# PowerSupply.net
KiCad netlist of a schematic drawn in Altium Designer
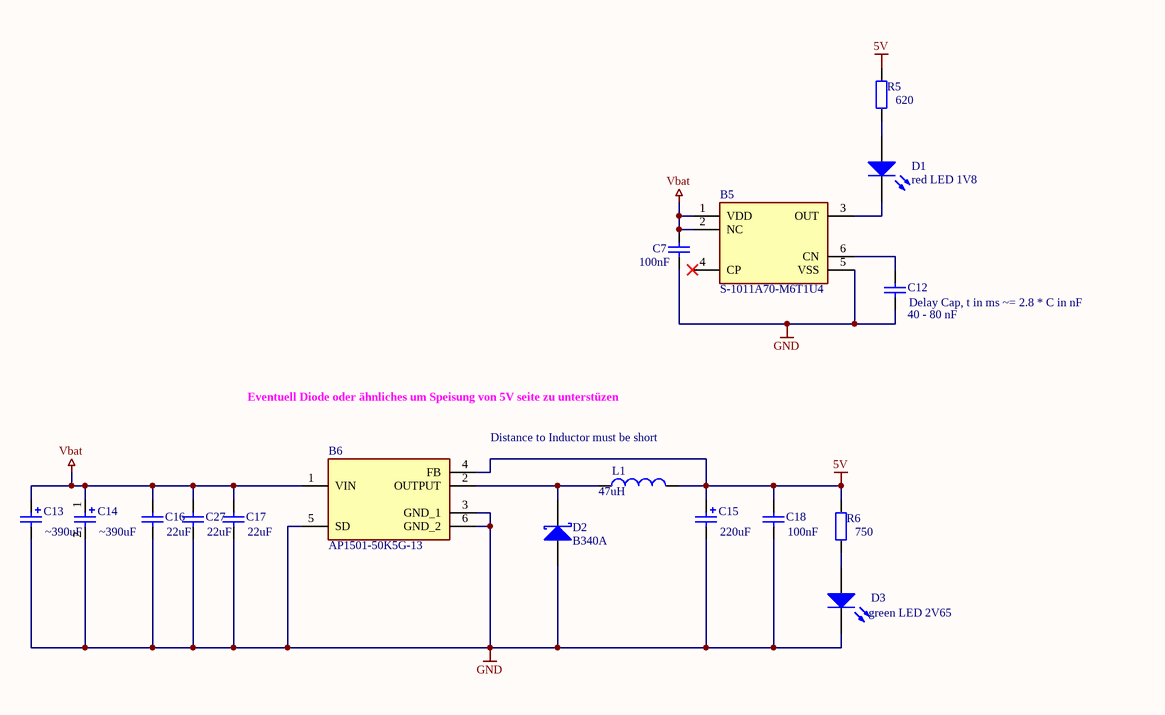
[diagram p0: PowerSupply.SchDoc]

(export (version "E")
  (design (tool "Eeschema 10.0.6"))
  (components
    (comp (ref "B5")
      (value "S-1011A70-M6T1U4")
      (footprint "SOT95P275X135-6N")
      (description "Supervisory Circuits VOLTAGE DETECTOR")
      (fields (field (name "MOUSER PART NUMBER") "628-S-1011A70-M6T1U4"))
      (libsource (lib "SchematicLib") (part "S-1011A70-M6T1U4"))
    )
    (comp (ref "B6")
      (value "AP1501-50K5G-13")
      (footprint "AP150150K5G13")
      (description "IC REG BUCK 5V 3A TO263-5")
      (fields (field (name "MOUSER PART NUMBER") "621-AP1501-50K5G-13"))
      (libsource (lib "SchematicLib") (part "AP1501-50K5G-13"))
    )
    (comp (ref "C7")
      (value "100nF")
      (footprint "0805_Lorin")
      (description "Capacitor")
      (fields (field (name "Comment") "Cap") (field (name "PUBLISHER") "Altium Limited"))
      (libsource (lib "Miscellaneous Devices") (part "Cap"))
    )
    (comp (ref "C12")
      (value "40 - 80 nF")
      (footprint "0805_Lorin")
      (description "Capacitor")
      (fields (field (name "Comment") "Cap") (field (name "PUBLISHER") "Altium Limited"))
      (libsource (lib "Miscellaneous Devices") (part "Cap"))
    )
    (comp (ref "C13")
      (value "~390uF")
      (footprint "CAP390uF")
      (description "Polarized Capacitor (Axial)")
      (fields (field (name "Comment") "Cap Pol2") (field (name "PUBLISHER") "Altium Limited"))
      (libsource (lib "Miscellaneous Devices") (part "Cap Pol2"))
    )
    (comp (ref "C14")
      (value "~390uF")
      (footprint "CAP390uF")
      (description "Polarized Capacitor (Axial)")
      (fields (field (name "Comment") "Cap Pol2") (field (name "PUBLISHER") "Altium Limited"))
      (libsource (lib "") (part "Cap Pol2_1"))
    )
    (comp (ref "C15")
      (value "220uF")
      (footprint "CAP220uF")
      (description "Polarized Capacitor (Axial)")
      (fields (field (name "Comment") "Cap Pol2") (field (name "PUBLISHER") "Altium Limited"))
      (libsource (lib "Miscellaneous Devices") (part "Cap Pol2"))
    )
    (comp (ref "C16")
      (value "22uF")
      (footprint "0805_Lorin")
      (description "Capacitor")
      (fields (field (name "Comment") "Cap") (field (name "PUBLISHER") "Altium Limited"))
      (libsource (lib "Miscellaneous Devices") (part "Cap"))
    )
    (comp (ref "C17")
      (value "22uF")
      (footprint "0805_Lorin")
      (description "Capacitor")
      (fields (field (name "Comment") "Cap") (field (name "PUBLISHER") "Altium Limited"))
      (libsource (lib "Miscellaneous Devices") (part "Cap"))
    )
    (comp (ref "C18")
      (value "100nF")
      (footprint "0805_Lorin")
      (description "Capacitor")
      (fields (field (name "Comment") "Cap") (field (name "PUBLISHER") "Altium Limited"))
      (libsource (lib "Miscellaneous Devices") (part "Cap"))
    )
    (comp (ref "C27")
      (value "22uF")
      (footprint "0805_Lorin")
      (description "Capacitor")
      (fields (field (name "Comment") "Cap") (field (name "PUBLISHER") "Altium Limited"))
      (libsource (lib "Miscellaneous Devices") (part "Cap"))
    )
    (comp (ref "D1")
      (value "red LED 1V8")
      (footprint "LEDC2012X75M")
      (description "Typical INFRARED GaAs LED")
      (fields (field (name "PUBLISHER") "Altium Limited"))
      (libsource (lib "Miscellaneous Devices") (part "LED0"))
    )
    (comp (ref "D2")
      (value "B340A")
      (footprint "SODFL5226X110M")
      (description "Schottky Diode")
      (fields (field (name "PUBLISHER") "Altium Limited"))
      (libsource (lib "Miscellaneous Devices") (part "D Schottky"))
    )
    (comp (ref "D3")
      (value "green LED 2V65")
      (footprint "LEDC2012X75M")
      (description "Typical INFRARED GaAs LED")
      (fields (field (name "PUBLISHER") "Altium Limited"))
      (libsource (lib "Miscellaneous Devices") (part "LED0"))
    )
    (comp (ref "L1")
      (value "47uH")
      (footprint "Inductor")
      (description "Inductor")
      (fields (field (name "PUBLISHER") "Altium Limited"))
      (libsource (lib "Miscellaneous Devices") (part "Inductor"))
    )
    (comp (ref "R5")
      (value "620")
      (footprint "0805_Lorin")
      (description "Resistor")
      (fields (field (name "Comment") "Res2") (field (name "PUBLISHER") "Altium Limited"))
      (libsource (lib "Miscellaneous Devices") (part "Res2"))
    )
    (comp (ref "R6")
      (value "750")
      (footprint "0805_Lorin")
      (description "Resistor")
      (fields (field (name "Comment") "Res2") (field (name "PUBLISHER") "Altium Limited"))
      (libsource (lib "Miscellaneous Devices") (part "Res2"))
    )
  )
  (nets
    (net (code "1") (name "5V") (class "Default")
      (node (ref "B6") (pin "4") (pinfunction "FB_4") (pintype "passive"))
      (node (ref "C15") (pin "1") (pinfunction "1_1") (pintype "passive"))
      (node (ref "C18") (pin "2") (pinfunction "2_2") (pintype "passive"))
      (node (ref "L1") (pin "2") (pinfunction "2_2") (pintype "passive"))
      (node (ref "R5") (pin "2") (pinfunction "2_2") (pintype "passive"))
      (node (ref "R6") (pin "2") (pinfunction "2_2") (pintype "passive"))
    )
    (net (code "2") (name "GND") (class "Default")
      (node (ref "B5") (pin "5") (pinfunction "VSS_5") (pintype "passive"))
      (node (ref "B6") (pin "3") (pinfunction "GND_1_3") (pintype "passive"))
      (node (ref "B6") (pin "5") (pinfunction "SD_5") (pintype "passive"))
      (node (ref "B6") (pin "6") (pinfunction "GND_2_6") (pintype "passive"))
      (node (ref "C12") (pin "1") (pinfunction "1_1") (pintype "passive"))
      (node (ref "C13") (pin "2") (pinfunction "2_2") (pintype "passive"))
      (node (ref "C14") (pin "2") (pinfunction "2_2") (pintype "passive"))
      (node (ref "C15") (pin "2") (pinfunction "2_2") (pintype "passive"))
      (node (ref "C16") (pin "1") (pinfunction "1_1") (pintype "passive"))
      (node (ref "C17") (pin "1") (pinfunction "1_1") (pintype "passive"))
      (node (ref "C18") (pin "1") (pinfunction "1_1") (pintype "passive"))
      (node (ref "C27") (pin "1") (pinfunction "1_1") (pintype "passive"))
      (node (ref "C7") (pin "1") (pinfunction "1_1") (pintype "passive"))
      (node (ref "D2") (pin "1") (pinfunction "A_1") (pintype "passive"))
      (node (ref "D3") (pin "2") (pinfunction "K_2") (pintype "passive"))
    )
    (net (code "3") (name "Net-(B5-CN)") (class "Default")
      (node (ref "B5") (pin "6") (pinfunction "CN_6") (pintype "passive"))
      (node (ref "C12") (pin "2") (pinfunction "2_2") (pintype "passive"))
    )
    (net (code "4") (name "Net-(B5-OUT)") (class "Default")
      (node (ref "B5") (pin "3") (pinfunction "OUT_3") (pintype "passive"))
      (node (ref "D1") (pin "2") (pinfunction "K_2") (pintype "passive"))
    )
    (net (code "5") (name "Net-(B6-OUTPUT)") (class "Default")
      (node (ref "B6") (pin "2") (pinfunction "OUTPUT_2") (pintype "passive"))
      (node (ref "D2") (pin "2") (pinfunction "K_2") (pintype "passive"))
      (node (ref "L1") (pin "1") (pinfunction "1_1") (pintype "passive"))
    )
    (net (code "6") (name "Net-(D1-A)") (class "Default")
      (node (ref "D1") (pin "1") (pinfunction "A_1") (pintype "passive"))
      (node (ref "R5") (pin "1") (pinfunction "1_1") (pintype "passive"))
    )
    (net (code "7") (name "Net-(D3-A)") (class "Default")
      (node (ref "D3") (pin "1") (pinfunction "A_1") (pintype "passive"))
      (node (ref "R6") (pin "1") (pinfunction "1_1") (pintype "passive"))
    )
    (net (code "8") (name "Vbat") (class "Default")
      (node (ref "B5") (pin "1") (pinfunction "VDD_1") (pintype "passive"))
      (node (ref "B5") (pin "2") (pinfunction "NC_2") (pintype "passive"))
      (node (ref "B6") (pin "1") (pinfunction "VIN_1") (pintype "passive"))
      (node (ref "C13") (pin "1") (pinfunction "1_1") (pintype "passive"))
      (node (ref "C14") (pin "1") (pinfunction "1_1") (pintype "passive"))
      (node (ref "C16") (pin "2") (pinfunction "2_2") (pintype "passive"))
      (node (ref "C17") (pin "2") (pinfunction "2_2") (pintype "passive"))
      (node (ref "C27") (pin "2") (pinfunction "2_2") (pintype "passive"))
      (node (ref "C7") (pin "2") (pinfunction "2_2") (pintype "passive"))
    )
    (net (code "9") (name "unconnected-(B5-CP-Pad4)") (class "Default")
      (node (ref "B5") (pin "4") (pinfunction "CP_4") (pintype "passive+no_connect"))
    )
  )
)
